# tracksoar_programmer.net
KiCad netlist of a schematic drawn in EAGLE
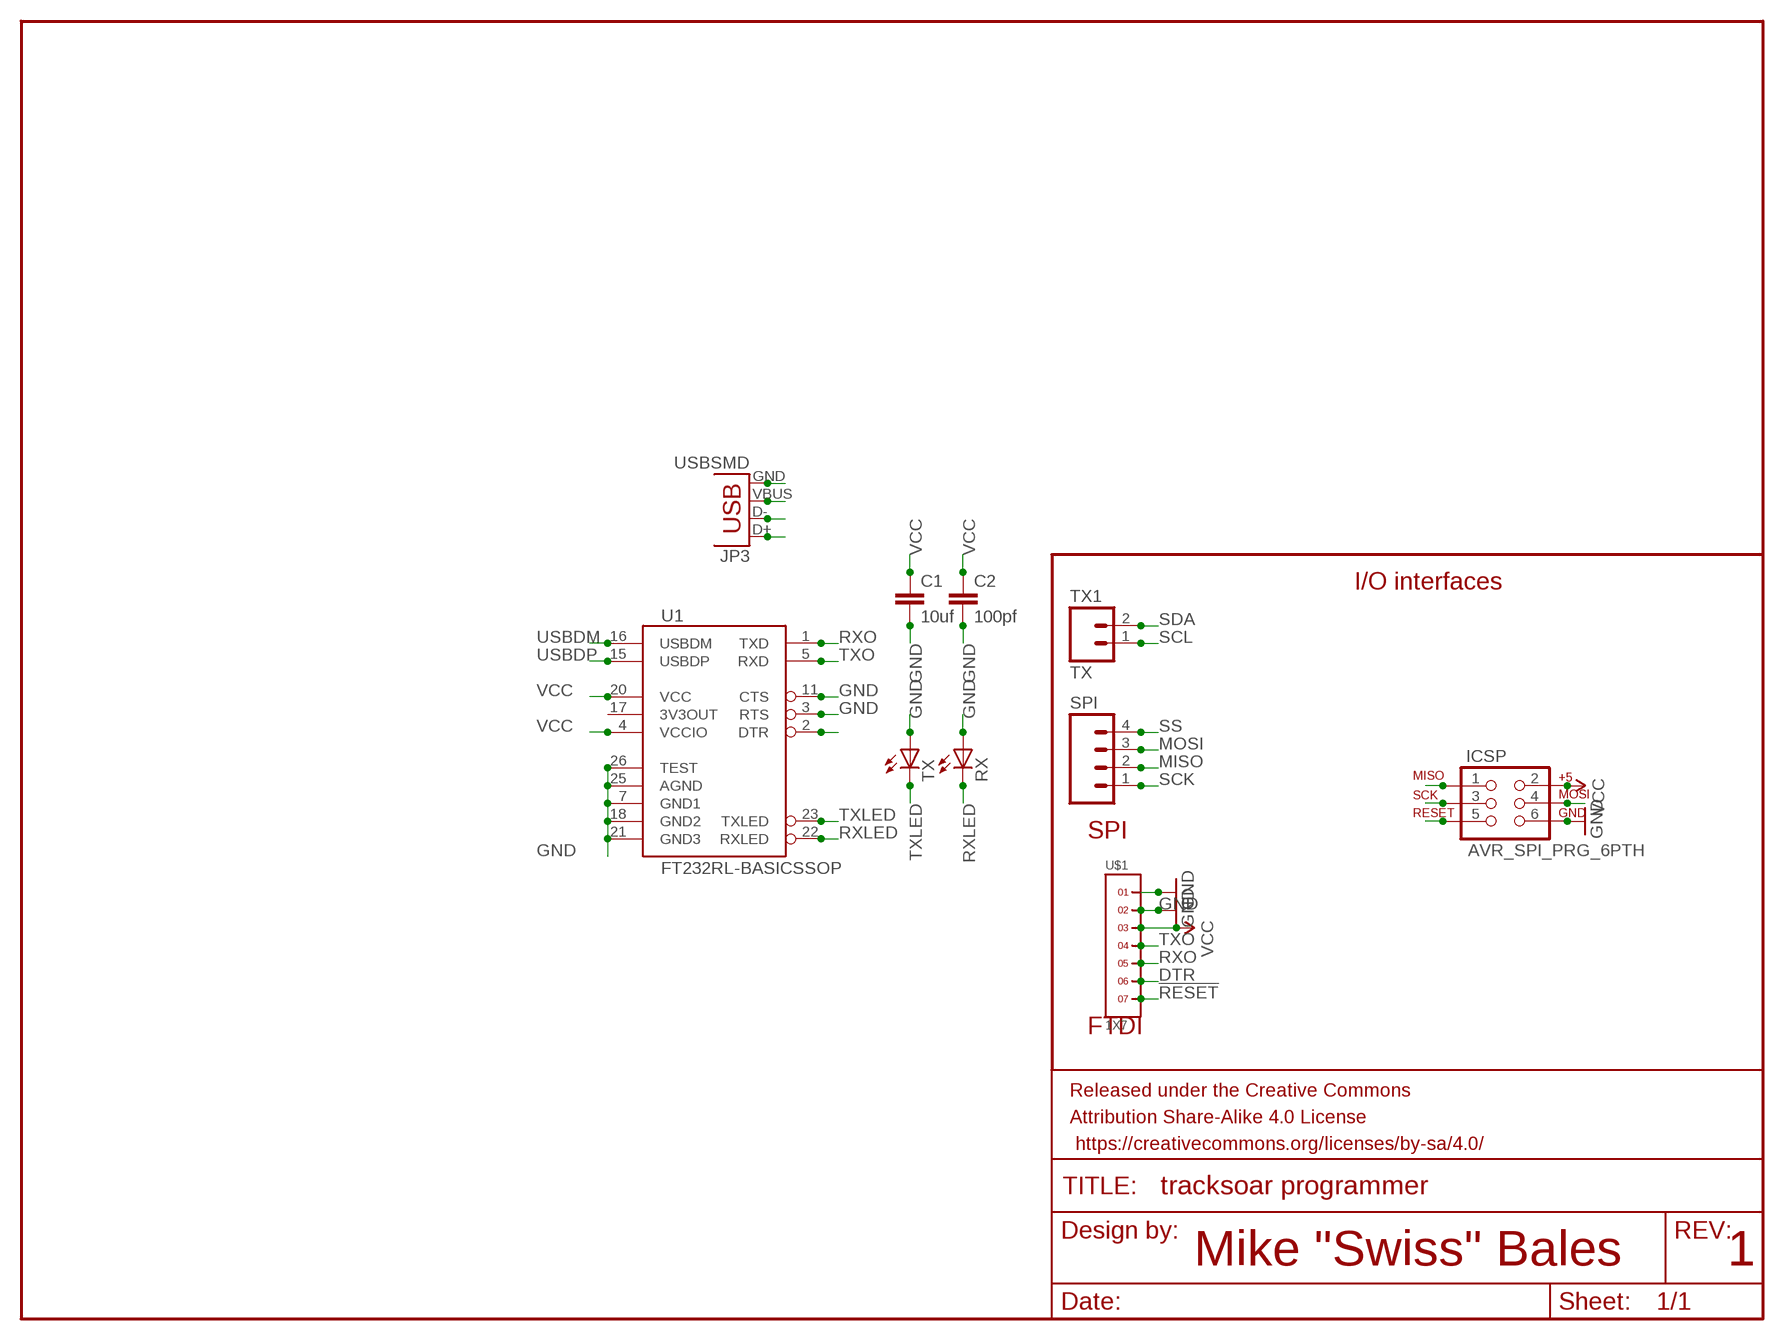
[diagram p0: schematic, sheet 1]

(export (version "E")
  (design (tool "Eeschema 10.0.6"))
  (components
    (comp (ref "C1")
      (value "10uf")
      (footprint "eagle-import:0805")
      (libsource (lib "eagle-import") (part "CAP0805"))
    )
    (comp (ref "C2")
      (value "100pf")
      (footprint "eagle-import:0805")
      (libsource (lib "eagle-import") (part "CAP0805"))
    )
    (comp (ref "FRAME1")
      (value "FRAME-LETTER")
      (footprint "eagle-import:CREATIVE_COMMONS")
      (libsource (lib "eagle-import") (part "FRAME-LETTER"))
    )
    (comp (ref "ICSP")
      (value "AVR_SPI_PRG_6PTH")
      (footprint "eagle-import:2X3")
      (libsource (lib "eagle-import") (part "AVR_SPI_PRG_6PTH"))
    )
    (comp (ref "JP3")
      (value "USBSMD")
      (footprint "eagle-import:USB-MINIB")
      (libsource (lib "eagle-import") (part "USBSMD"))
    )
    (comp (ref "RX")
      (value "LEDCHIP-LED0805")
      (footprint "eagle-import:CHIP-LED0805")
      (libsource (lib "eagle-import") (part "LEDCHIP-LED0805"))
    )
    (comp (ref "SPI")
      (value "M04JST-PTH-VERT")
      (footprint "eagle-import:JST-4-PTH-VERT")
      (libsource (lib "eagle-import") (part "M04JST-PTH-VERT"))
    )
    (comp (ref "TX")
      (value "LEDCHIP-LED0805")
      (footprint "eagle-import:CHIP-LED0805")
      (libsource (lib "eagle-import") (part "LEDCHIP-LED0805"))
    )
    (comp (ref "TX1")
      (value "TX")
      (footprint "eagle-import:JST-2-PTH-VERT")
      (libsource (lib "eagle-import") (part "M02JST-PTH-VERT"))
    )
    (comp (ref "U$1")
      (value "1X7")
      (footprint "eagle-import:1X7")
      (libsource (lib "eagle-import") (part "1X7"))
    )
    (comp (ref "U1")
      (value "FT232RL-BASICSSOP")
      (footprint "eagle-import:SSOP28DB")
      (libsource (lib "eagle-import") (part "FT232RL-BASICSSOP"))
    )
  )
  (nets
    (net (code "1") (name "/DTR") (class "Default")
      (node (ref "U$1") (pin "6") (pinfunction "6_6") (pintype "bidirectional"))
      (node (ref "U1") (pin "2") (pinfunction "DTR_2") (pintype "bidirectional"))
    )
    (net (code "2") (name "/MISO") (class "Default")
      (node (ref "ICSP") (pin "1") (pinfunction "1_1") (pintype "passive"))
      (node (ref "SPI") (pin "2") (pinfunction "2_2") (pintype "passive"))
    )
    (net (code "3") (name "/MOSI") (class "Default")
      (node (ref "ICSP") (pin "4") (pinfunction "4_4") (pintype "passive"))
      (node (ref "SPI") (pin "3") (pinfunction "3_3") (pintype "passive"))
    )
    (net (code "4") (name "/RXLED") (class "Default")
      (node (ref "RX") (pin "C") (pinfunction "C_C") (pintype "passive"))
      (node (ref "U1") (pin "22") (pinfunction "RXLED_22") (pintype "bidirectional"))
    )
    (net (code "5") (name "/RXO") (class "Default")
      (node (ref "U$1") (pin "5") (pinfunction "5_5") (pintype "bidirectional"))
      (node (ref "U1") (pin "1") (pinfunction "TXD_1") (pintype "output"))
    )
    (net (code "6") (name "/SCK") (class "Default")
      (node (ref "ICSP") (pin "3") (pinfunction "3_3") (pintype "passive"))
      (node (ref "SPI") (pin "1") (pinfunction "1_1") (pintype "passive"))
    )
    (net (code "7") (name "/SCL") (class "Default")
      (node (ref "TX1") (pin "1") (pinfunction "1_1") (pintype "passive"))
    )
    (net (code "8") (name "/SDA") (class "Default")
      (node (ref "TX1") (pin "2") (pinfunction "2_2") (pintype "passive"))
    )
    (net (code "9") (name "/SS") (class "Default")
      (node (ref "SPI") (pin "4") (pinfunction "4_4") (pintype "passive"))
    )
    (net (code "10") (name "/TXLED") (class "Default")
      (node (ref "TX") (pin "C") (pinfunction "C_C") (pintype "passive"))
      (node (ref "U1") (pin "23") (pinfunction "TXLED_23") (pintype "bidirectional"))
    )
    (net (code "11") (name "/TXO") (class "Default")
      (node (ref "U$1") (pin "4") (pinfunction "4_4") (pintype "bidirectional"))
      (node (ref "U1") (pin "5") (pinfunction "RXD_5") (pintype "input"))
    )
    (net (code "12") (name "/USBDM") (class "Default")
      (node (ref "JP3") (pin "D-") (pinfunction "D-_D-") (pintype "bidirectional"))
      (node (ref "U1") (pin "16") (pinfunction "USBDM_16") (pintype "bidirectional"))
    )
    (net (code "13") (name "/USBDP") (class "Default")
      (node (ref "JP3") (pin "D+") (pinfunction "D+_D+") (pintype "bidirectional"))
      (node (ref "U1") (pin "15") (pinfunction "USBDP_15") (pintype "bidirectional"))
    )
    (net (code "14") (name "/~{RESET}") (class "Default")
      (node (ref "ICSP") (pin "5") (pinfunction "5_5") (pintype "passive"))
      (node (ref "U$1") (pin "7") (pinfunction "7_7") (pintype "bidirectional"))
    )
    (net (code "15") (name "GND") (class "Default")
      (node (ref "C1") (pin "2") (pinfunction "2_2") (pintype "passive"))
      (node (ref "C2") (pin "2") (pinfunction "2_2") (pintype "passive"))
      (node (ref "ICSP") (pin "6") (pinfunction "6_6") (pintype "passive"))
      (node (ref "JP3") (pin "GND") (pinfunction "GND_GND") (pintype "bidirectional"))
      (node (ref "RX") (pin "A") (pinfunction "A_A") (pintype "passive"))
      (node (ref "TX") (pin "A") (pinfunction "A_A") (pintype "passive"))
      (node (ref "U$1") (pin "1") (pinfunction "1_1") (pintype "bidirectional"))
      (node (ref "U$1") (pin "2") (pinfunction "2_2") (pintype "bidirectional"))
      (node (ref "U1") (pin "11") (pinfunction "CTS_11") (pintype "bidirectional"))
      (node (ref "U1") (pin "18") (pinfunction "GND2_18") (pintype "power_in"))
      (node (ref "U1") (pin "21") (pinfunction "GND3_21") (pintype "power_in"))
      (node (ref "U1") (pin "25") (pinfunction "AGND_25") (pintype "power_in"))
      (node (ref "U1") (pin "26") (pinfunction "TEST_26") (pintype "input"))
      (node (ref "U1") (pin "3") (pinfunction "RTS_3") (pintype "bidirectional"))
      (node (ref "U1") (pin "7") (pinfunction "GND1_7") (pintype "power_in"))
    )
    (net (code "16") (name "VCC") (class "Default")
      (node (ref "C1") (pin "1") (pinfunction "1_1") (pintype "passive"))
      (node (ref "C2") (pin "1") (pinfunction "1_1") (pintype "passive"))
      (node (ref "ICSP") (pin "2") (pinfunction "2_2") (pintype "passive"))
      (node (ref "JP3") (pin "VBUS") (pinfunction "VBUS_VBUS") (pintype "bidirectional"))
      (node (ref "U$1") (pin "3") (pinfunction "3_3") (pintype "bidirectional"))
      (node (ref "U1") (pin "20") (pinfunction "VCC_20") (pintype "power_in"))
      (node (ref "U1") (pin "4") (pinfunction "VCCIO_4") (pintype "power_in"))
    )
    (net (code "17") (name "unconnected-(U1-3V3OUT-Pad17)") (class "Default")
      (node (ref "U1") (pin "17") (pinfunction "3V3OUT_17") (pintype "output"))
    )
  )
)
